# power_board.net
KiCad netlist of a schematic drawn in EAGLE
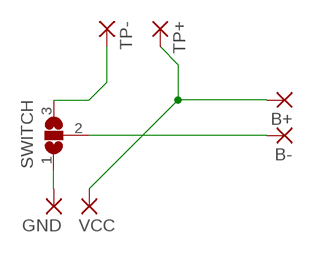
[diagram p0: schematic, sheet 1]

(export (version "E")
  (design (tool "Eeschema 10.0.6"))
  (components
    (comp (ref "B+")
      (value "SMD2")
      (footprint "eagle-import:SMD1,27-2,54")
      (libsource (lib "eagle-import") (part "SMD2"))
    )
    (comp (ref "B-")
      (value "SMD2")
      (footprint "eagle-import:SMD1,27-2,54")
      (libsource (lib "eagle-import") (part "SMD2"))
    )
    (comp (ref "GND")
      (value "SMD2")
      (footprint "eagle-import:SMD1,27-2,54")
      (libsource (lib "eagle-import") (part "SMD2"))
    )
    (comp (ref "SWITCH")
      (value "SJ2WW")
      (footprint "eagle-import:SJ_2W")
      (libsource (lib "eagle-import") (part "SJ2WW"))
    )
    (comp (ref "TP+")
      (value "SMD2")
      (footprint "eagle-import:SMD1,27-2,54")
      (libsource (lib "eagle-import") (part "SMD2"))
    )
    (comp (ref "TP-")
      (value "SMD2")
      (footprint "eagle-import:SMD1,27-2,54")
      (libsource (lib "eagle-import") (part "SMD2"))
    )
    (comp (ref "VCC")
      (value "SMD2")
      (footprint "eagle-import:SMD1,27-2,54")
      (libsource (lib "eagle-import") (part "SMD2"))
    )
  )
  (nets
    (net (code "1") (name "Net-(B+-P)") (class "Default")
      (node (ref "B+") (pin "1") (pinfunction "P_1") (pintype "passive"))
      (node (ref "TP+") (pin "1") (pinfunction "P_1") (pintype "passive"))
      (node (ref "VCC") (pin "1") (pinfunction "P_1") (pintype "passive"))
    )
    (net (code "2") (name "Net-(B--P)") (class "Default")
      (node (ref "B-") (pin "1") (pinfunction "P_1") (pintype "passive"))
      (node (ref "SWITCH") (pin "2") (pinfunction "2_2") (pintype "passive"))
    )
    (net (code "3") (name "Net-(GND-P)") (class "Default")
      (node (ref "GND") (pin "1") (pinfunction "P_1") (pintype "passive"))
      (node (ref "SWITCH") (pin "1") (pinfunction "1_1") (pintype "passive"))
    )
    (net (code "4") (name "Net-(TP--P)") (class "Default")
      (node (ref "SWITCH") (pin "3") (pinfunction "3_3") (pintype "passive"))
      (node (ref "TP-") (pin "1") (pinfunction "P_1") (pintype "passive"))
    )
  )
)
